# Connector.net
KiCad netlist of a schematic drawn in EAGLE
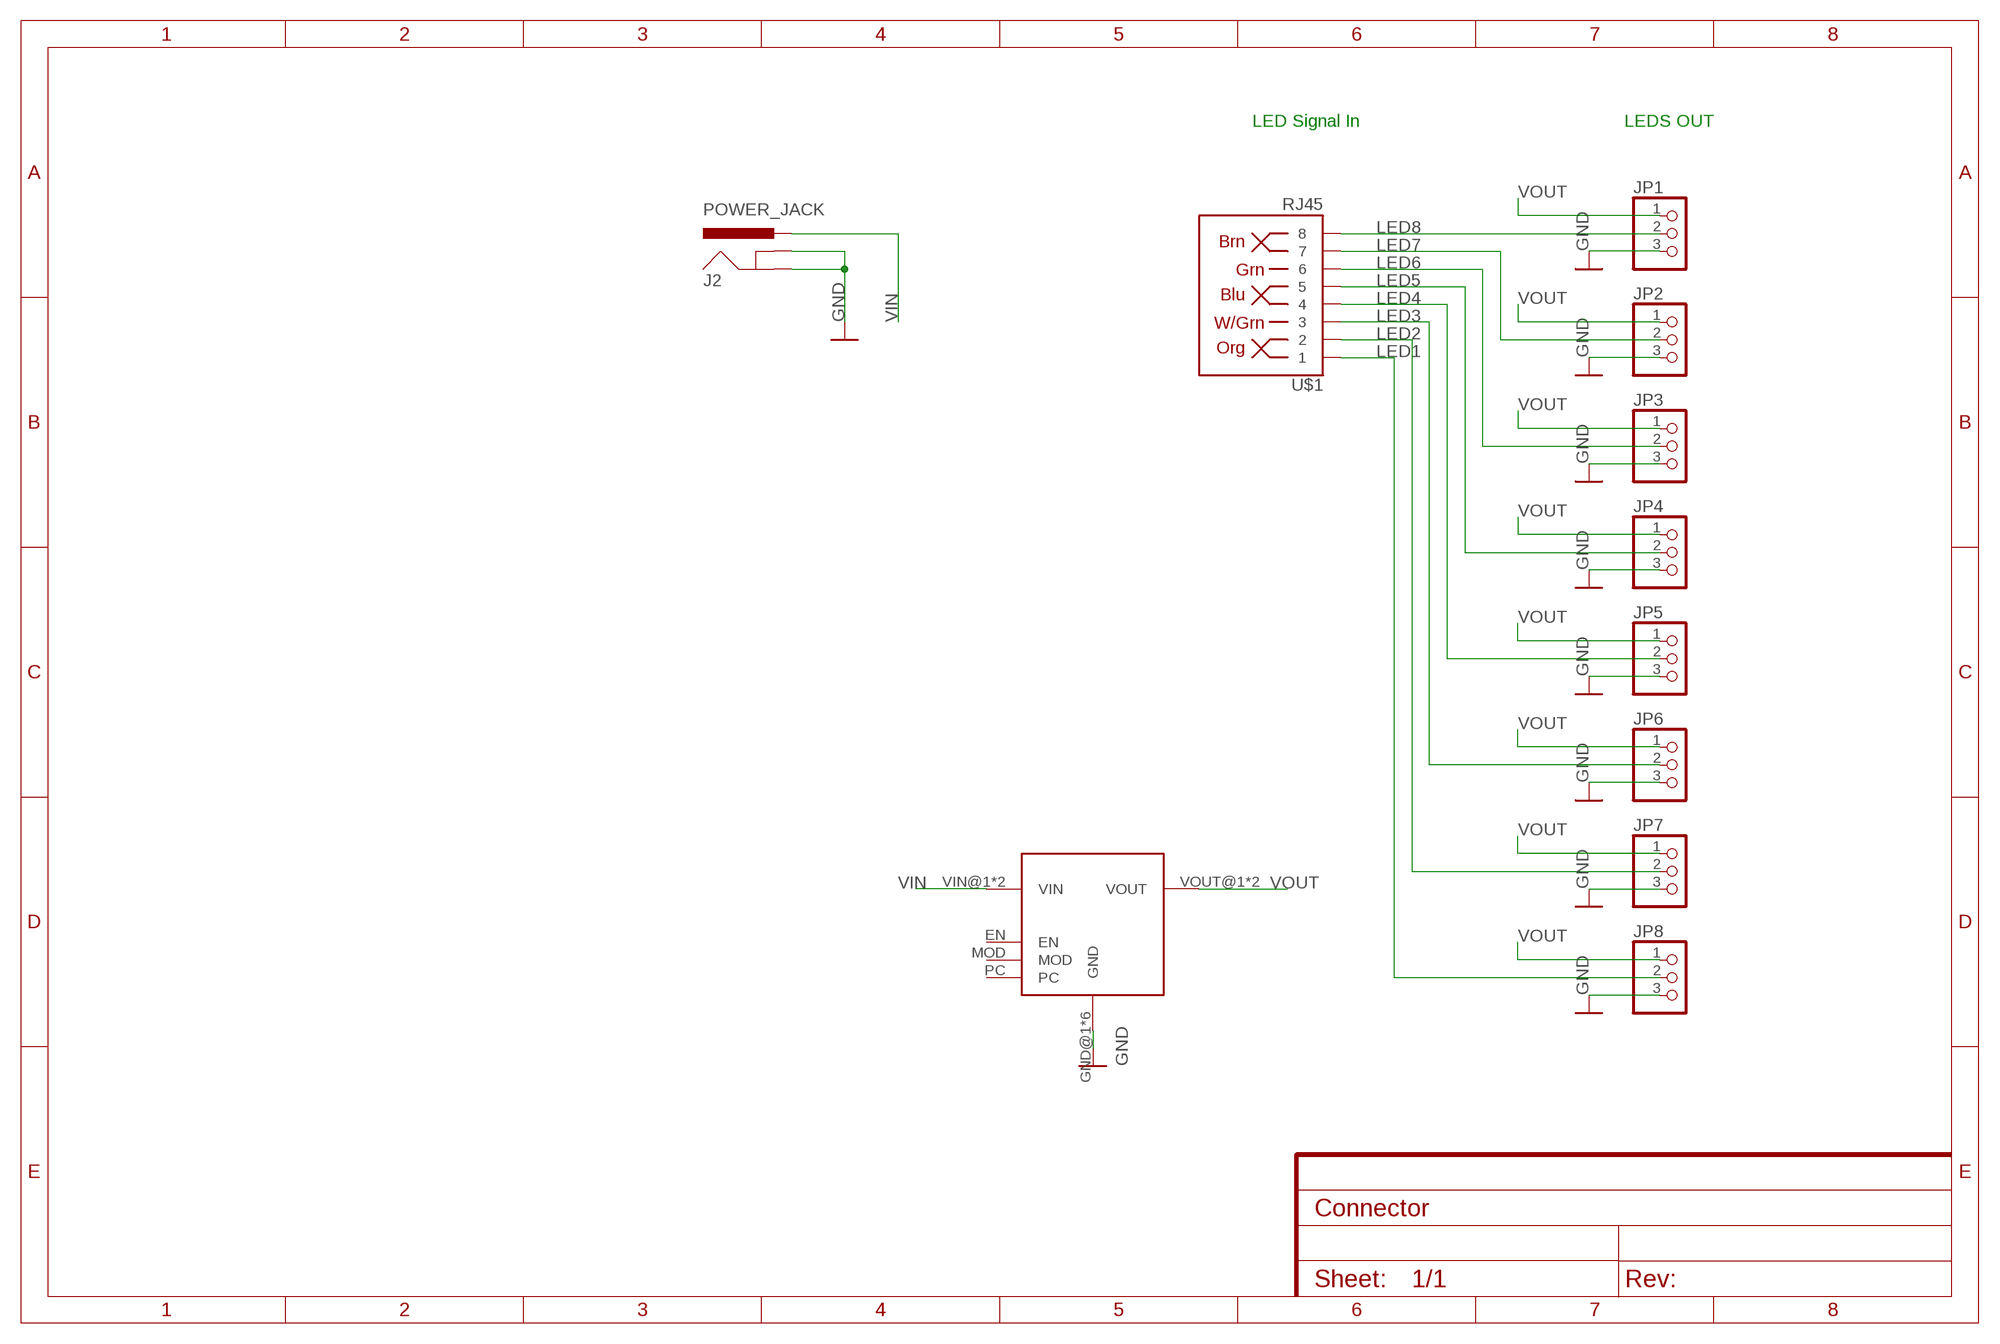
[diagram p0: schematic, sheet 1]

(export (version "E")
  (design (tool "Eeschema 10.0.6"))
  (components
    (comp (ref "J2")
      (value "POWER_JACK")
      (footprint "eagle-import:POWER_JACK_PTH")
      (libsource (lib "eagle-import") (part "POWER_JACK"))
    )
    (comp (ref "JP1")
      (value "PINHD-1X3")
      (footprint "eagle-import:1X03")
      (libsource (lib "eagle-import") (part "PINHD-1X3"))
    )
    (comp (ref "JP2")
      (value "PINHD-1X3")
      (footprint "eagle-import:1X03")
      (libsource (lib "eagle-import") (part "PINHD-1X3"))
    )
    (comp (ref "JP3")
      (value "PINHD-1X3")
      (footprint "eagle-import:1X03")
      (libsource (lib "eagle-import") (part "PINHD-1X3"))
    )
    (comp (ref "JP4")
      (value "PINHD-1X3")
      (footprint "eagle-import:1X03")
      (libsource (lib "eagle-import") (part "PINHD-1X3"))
    )
    (comp (ref "JP5")
      (value "PINHD-1X3")
      (footprint "eagle-import:1X03")
      (libsource (lib "eagle-import") (part "PINHD-1X3"))
    )
    (comp (ref "JP6")
      (value "PINHD-1X3")
      (footprint "eagle-import:1X03")
      (libsource (lib "eagle-import") (part "PINHD-1X3"))
    )
    (comp (ref "JP7")
      (value "PINHD-1X3")
      (footprint "eagle-import:1X03")
      (libsource (lib "eagle-import") (part "PINHD-1X3"))
    )
    (comp (ref "JP8")
      (value "PINHD-1X3")
      (footprint "eagle-import:1X03")
      (libsource (lib "eagle-import") (part "PINHD-1X3"))
    )
    (comp (ref "U$1")
      (value "RJ45")
      (footprint "eagle-import:RJ45_WINGS")
      (libsource (lib "eagle-import") (part "RJ45"))
    )
    (comp (ref "U$2")
      (value "5V-15A-VOLTAGE_CONVERTER")
      (footprint "eagle-import:D24V150F")
      (libsource (lib "eagle-import") (part "5V-15A-VOLTAGE_CONVERTER"))
    )
  )
  (nets
    (net (code "1") (name "/LED1") (class "Default")
      (node (ref "JP8") (pin "2") (pinfunction "2_2") (pintype "passive"))
      (node (ref "U$1") (pin "1") (pinfunction "1_1") (pintype "bidirectional"))
    )
    (net (code "2") (name "/LED2") (class "Default")
      (node (ref "JP7") (pin "2") (pinfunction "2_2") (pintype "passive"))
      (node (ref "U$1") (pin "2") (pinfunction "2_2") (pintype "bidirectional"))
    )
    (net (code "3") (name "/LED3") (class "Default")
      (node (ref "JP6") (pin "2") (pinfunction "2_2") (pintype "passive"))
      (node (ref "U$1") (pin "3") (pinfunction "3_3") (pintype "bidirectional"))
    )
    (net (code "4") (name "/LED4") (class "Default")
      (node (ref "JP5") (pin "2") (pinfunction "2_2") (pintype "passive"))
      (node (ref "U$1") (pin "4") (pinfunction "4_4") (pintype "bidirectional"))
    )
    (net (code "5") (name "/LED5") (class "Default")
      (node (ref "JP4") (pin "2") (pinfunction "2_2") (pintype "passive"))
      (node (ref "U$1") (pin "5") (pinfunction "5_5") (pintype "bidirectional"))
    )
    (net (code "6") (name "/LED6") (class "Default")
      (node (ref "JP3") (pin "2") (pinfunction "2_2") (pintype "passive"))
      (node (ref "U$1") (pin "6") (pinfunction "6_6") (pintype "bidirectional"))
    )
    (net (code "7") (name "/LED7") (class "Default")
      (node (ref "JP2") (pin "2") (pinfunction "2_2") (pintype "passive"))
      (node (ref "U$1") (pin "7") (pinfunction "7_7") (pintype "bidirectional"))
    )
    (net (code "8") (name "/LED8") (class "Default")
      (node (ref "JP1") (pin "2") (pinfunction "2_2") (pintype "passive"))
      (node (ref "U$1") (pin "8") (pinfunction "8_8") (pintype "bidirectional"))
    )
    (net (code "9") (name "/VIN") (class "Default")
      (node (ref "J2") (pin "PWR") (pinfunction "PWR_PWR") (pintype "bidirectional"))
      (node (ref "U$2") (pin "VIN@1") (pinfunction "VIN_VIN@1") (pintype "bidirectional"))
      (node (ref "U$2") (pin "VIN@2") (pinfunction "VIN_VIN@2") (pintype "bidirectional"))
    )
    (net (code "10") (name "/VOUT") (class "Default")
      (node (ref "JP1") (pin "1") (pinfunction "1_1") (pintype "passive"))
      (node (ref "JP2") (pin "1") (pinfunction "1_1") (pintype "passive"))
      (node (ref "JP3") (pin "1") (pinfunction "1_1") (pintype "passive"))
      (node (ref "JP4") (pin "1") (pinfunction "1_1") (pintype "passive"))
      (node (ref "JP5") (pin "1") (pinfunction "1_1") (pintype "passive"))
      (node (ref "JP6") (pin "1") (pinfunction "1_1") (pintype "passive"))
      (node (ref "JP7") (pin "1") (pinfunction "1_1") (pintype "passive"))
      (node (ref "JP8") (pin "1") (pinfunction "1_1") (pintype "passive"))
      (node (ref "U$2") (pin "VOUT@1") (pinfunction "VOUT_VOUT@1") (pintype "bidirectional"))
      (node (ref "U$2") (pin "VOUT@2") (pinfunction "VOUT_VOUT@2") (pintype "bidirectional"))
    )
    (net (code "11") (name "GND") (class "Default")
      (node (ref "J2") (pin "GND") (pinfunction "GND_GND") (pintype "bidirectional"))
      (node (ref "J2") (pin "GNDBREAK") (pinfunction "GNDBREAK_GNDBREAK") (pintype "bidirectional"))
      (node (ref "JP1") (pin "3") (pinfunction "3_3") (pintype "passive"))
      (node (ref "JP2") (pin "3") (pinfunction "3_3") (pintype "passive"))
      (node (ref "JP3") (pin "3") (pinfunction "3_3") (pintype "passive"))
      (node (ref "JP4") (pin "3") (pinfunction "3_3") (pintype "passive"))
      (node (ref "JP5") (pin "3") (pinfunction "3_3") (pintype "passive"))
      (node (ref "JP6") (pin "3") (pinfunction "3_3") (pintype "passive"))
      (node (ref "JP7") (pin "3") (pinfunction "3_3") (pintype "passive"))
      (node (ref "JP8") (pin "3") (pinfunction "3_3") (pintype "passive"))
      (node (ref "U$2") (pin "GND@1") (pinfunction "GND_GND@1") (pintype "bidirectional"))
      (node (ref "U$2") (pin "GND@2") (pinfunction "GND_GND@2") (pintype "bidirectional"))
      (node (ref "U$2") (pin "GND@3") (pinfunction "GND_GND@3") (pintype "bidirectional"))
      (node (ref "U$2") (pin "GND@4") (pinfunction "GND_GND@4") (pintype "bidirectional"))
      (node (ref "U$2") (pin "GND@5") (pinfunction "GND_GND@5") (pintype "bidirectional"))
      (node (ref "U$2") (pin "GND@6") (pinfunction "GND_GND@6") (pintype "bidirectional"))
    )
    (net (code "12") (name "unconnected-(U$2-PadEN)") (class "Default")
      (node (ref "U$2") (pin "EN") (pinfunction "EN_EN") (pintype "bidirectional"))
    )
    (net (code "13") (name "unconnected-(U$2-PadMOD)") (class "Default")
      (node (ref "U$2") (pin "MOD") (pinfunction "MOD_MOD") (pintype "bidirectional"))
    )
    (net (code "14") (name "unconnected-(U$2-PadPC)") (class "Default")
      (node (ref "U$2") (pin "PC") (pinfunction "PC_PC") (pintype "bidirectional"))
    )
  )
)
